# HEBoard_AFE.net
KiCad netlist of a schematic drawn in Altium Designer
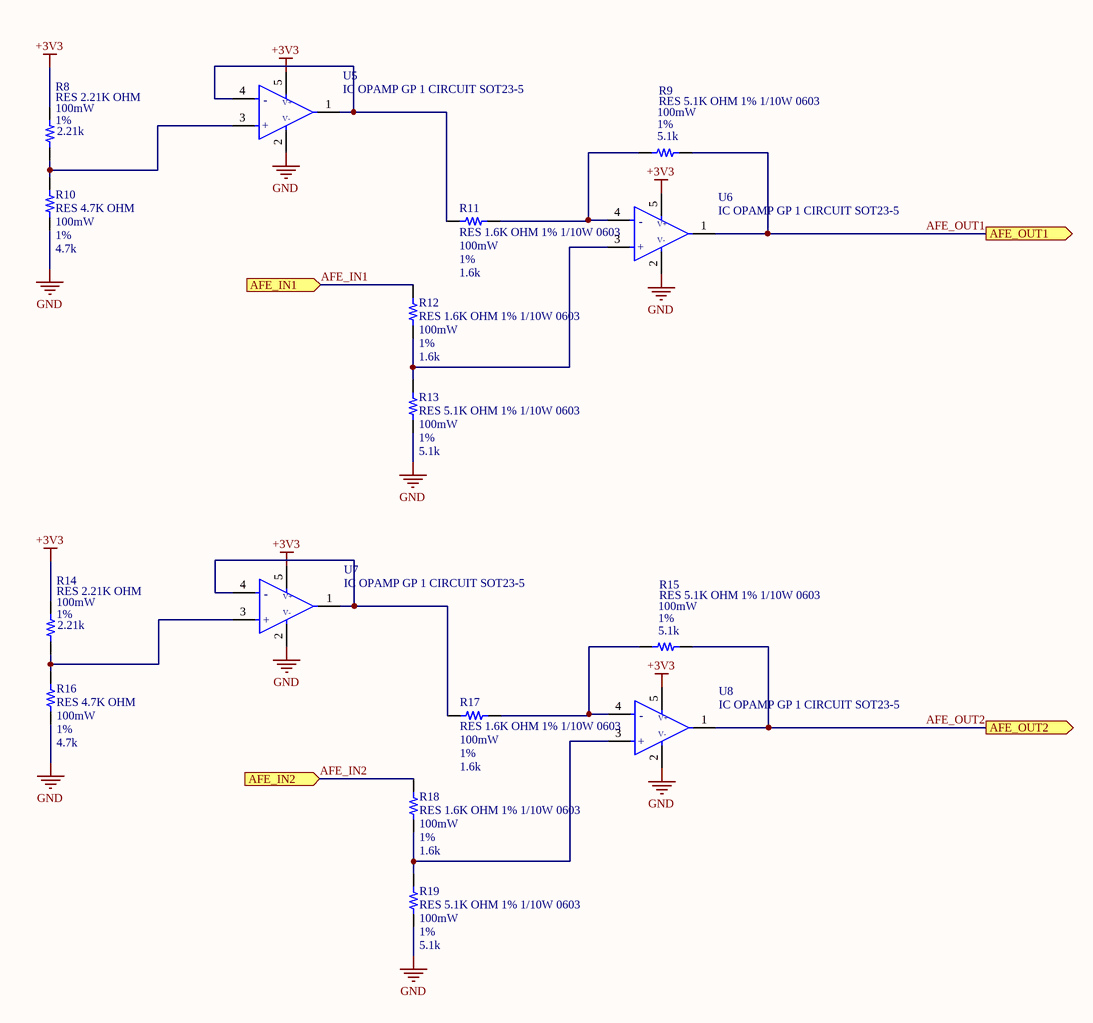
[diagram p0: HEBoard_AFE.SchDoc]

(export (version "E")
  (design (tool "Eeschema 10.0.6"))
  (components
    (comp (ref "R8")
      (value "RES 2.21K OHM")
      (footprint "RES 0603_1608")
      (fields
        (field (name "POWER RATING") "100mW")
        (field (name "TOLERANCE") "1%")
        (field (name "RESISTANCE") "2.21k")
      )
      (libsource (lib "Midnight Sun") (part "Resistor"))
    )
    (comp (ref "R9")
      (value "RES 5.1K OHM 1% 1/10W 0603")
      (footprint "RES 0603_1608")
      (description "5.1 kOhms ±1% 0.1W, 1/10W Chip Resistor 0603 (1608 Metric) Automotive AEC-Q200 Thick Film")
      (fields
        (field (name "POWER RATING") "100mW")
        (field (name "TOLERANCE") "1%")
        (field (name "RESISTANCE") "5.1k")
      )
      (libsource (lib "Midnight Sun") (part "Resistor"))
    )
    (comp (ref "R10")
      (value "RES 4.7K OHM")
      (footprint "RES 0603_1608")
      (fields
        (field (name "POWER RATING") "100mW")
        (field (name "TOLERANCE") "1%")
        (field (name "RESISTANCE") "4.7k")
      )
      (libsource (lib "Midnight Sun") (part "Resistor"))
    )
    (comp (ref "R11")
      (value "RES 1.6K OHM 1% 1/10W 0603")
      (footprint "RES 0603_1608")
      (description "1.6 kOhms ±1% 0.1W, 1/10W Chip Resistor 0603 (1608 Metric) Moisture Resistant Thick Film")
      (fields
        (field (name "POWER RATING") "100mW")
        (field (name "TOLERANCE") "1%")
        (field (name "RESISTANCE") "1.6k")
      )
      (libsource (lib "Midnight Sun") (part "Resistor"))
    )
    (comp (ref "R12")
      (value "RES 1.6K OHM 1% 1/10W 0603")
      (footprint "RES 0603_1608")
      (description "1.6 kOhms ±1% 0.1W, 1/10W Chip Resistor 0603 (1608 Metric) Moisture Resistant Thick Film")
      (fields
        (field (name "POWER RATING") "100mW")
        (field (name "TOLERANCE") "1%")
        (field (name "RESISTANCE") "1.6k")
      )
      (libsource (lib "Midnight Sun") (part "Resistor"))
    )
    (comp (ref "R13")
      (value "RES 5.1K OHM 1% 1/10W 0603")
      (footprint "RES 0603_1608")
      (description "5.1 kOhms ±1% 0.1W, 1/10W Chip Resistor 0603 (1608 Metric) Automotive AEC-Q200 Thick Film")
      (fields
        (field (name "POWER RATING") "100mW")
        (field (name "TOLERANCE") "1%")
        (field (name "RESISTANCE") "5.1k")
      )
      (libsource (lib "Midnight Sun") (part "Resistor"))
    )
    (comp (ref "R14")
      (value "RES 2.21K OHM")
      (footprint "RES 0603_1608")
      (fields
        (field (name "POWER RATING") "100mW")
        (field (name "TOLERANCE") "1%")
        (field (name "RESISTANCE") "2.21k")
      )
      (libsource (lib "Midnight Sun") (part "Resistor"))
    )
    (comp (ref "R15")
      (value "RES 5.1K OHM 1% 1/10W 0603")
      (footprint "RES 0603_1608")
      (description "5.1 kOhms ±1% 0.1W, 1/10W Chip Resistor 0603 (1608 Metric) Automotive AEC-Q200 Thick Film")
      (fields
        (field (name "POWER RATING") "100mW")
        (field (name "TOLERANCE") "1%")
        (field (name "RESISTANCE") "5.1k")
      )
      (libsource (lib "Midnight Sun") (part "Resistor"))
    )
    (comp (ref "R16")
      (value "RES 4.7K OHM")
      (footprint "RES 0603_1608")
      (fields
        (field (name "POWER RATING") "100mW")
        (field (name "TOLERANCE") "1%")
        (field (name "RESISTANCE") "4.7k")
      )
      (libsource (lib "Midnight Sun") (part "Resistor"))
    )
    (comp (ref "R17")
      (value "RES 1.6K OHM 1% 1/10W 0603")
      (footprint "RES 0603_1608")
      (description "1.6 kOhms ±1% 0.1W, 1/10W Chip Resistor 0603 (1608 Metric) Moisture Resistant Thick Film")
      (fields
        (field (name "POWER RATING") "100mW")
        (field (name "TOLERANCE") "1%")
        (field (name "RESISTANCE") "1.6k")
      )
      (libsource (lib "Midnight Sun") (part "Resistor"))
    )
    (comp (ref "R18")
      (value "RES 1.6K OHM 1% 1/10W 0603")
      (footprint "RES 0603_1608")
      (description "1.6 kOhms ±1% 0.1W, 1/10W Chip Resistor 0603 (1608 Metric) Moisture Resistant Thick Film")
      (fields
        (field (name "POWER RATING") "100mW")
        (field (name "TOLERANCE") "1%")
        (field (name "RESISTANCE") "1.6k")
      )
      (libsource (lib "Midnight Sun") (part "Resistor"))
    )
    (comp (ref "R19")
      (value "RES 5.1K OHM 1% 1/10W 0603")
      (footprint "RES 0603_1608")
      (description "5.1 kOhms ±1% 0.1W, 1/10W Chip Resistor 0603 (1608 Metric) Automotive AEC-Q200 Thick Film")
      (fields
        (field (name "POWER RATING") "100mW")
        (field (name "TOLERANCE") "1%")
        (field (name "RESISTANCE") "5.1k")
      )
      (libsource (lib "Midnight Sun") (part "Resistor"))
    )
    (comp (ref "U5")
      (value "IC OPAMP GP 1 CIRCUIT SOT23-5")
      (footprint "SOT 23-5")
      (description "General Purpose Amplifier 1 Circuit Rail-to-Rail SOT-23-5")
      (fields (field (name "MANUFACTURER PART NUMBER") "TLV9051IDBVR"))
      (libsource (lib "Midnight Sun") (part "Op-Amp 5pin-1"))
    )
    (comp (ref "U6")
      (value "IC OPAMP GP 1 CIRCUIT SOT23-5")
      (footprint "SOT 23-5")
      (description "General Purpose Amplifier 1 Circuit Rail-to-Rail SOT-23-5")
      (fields (field (name "MANUFACTURER PART NUMBER") "TLV9051IDBVR"))
      (libsource (lib "Midnight Sun") (part "Op-Amp 5pin-1"))
    )
    (comp (ref "U7")
      (value "IC OPAMP GP 1 CIRCUIT SOT23-5")
      (footprint "SOT 23-5")
      (description "General Purpose Amplifier 1 Circuit Rail-to-Rail SOT-23-5")
      (fields (field (name "MANUFACTURER PART NUMBER") "TLV9051IDBVR"))
      (libsource (lib "Midnight Sun") (part "Op-Amp 5pin-1"))
    )
    (comp (ref "U8")
      (value "IC OPAMP GP 1 CIRCUIT SOT23-5")
      (footprint "SOT 23-5")
      (description "General Purpose Amplifier 1 Circuit Rail-to-Rail SOT-23-5")
      (fields (field (name "MANUFACTURER PART NUMBER") "TLV9051IDBVR"))
      (libsource (lib "Midnight Sun") (part "Op-Amp 5pin-1"))
    )
  )
  (nets
    (net (code "1") (name "+3V3") (class "Default")
      (node (ref "R14") (pin "1") (pinfunction "1_1") (pintype "passive"))
      (node (ref "R8") (pin "1") (pinfunction "1_1") (pintype "passive"))
      (node (ref "U5") (pin "5") (pinfunction "V+_5") (pintype "power_in"))
      (node (ref "U6") (pin "5") (pinfunction "V+_5") (pintype "power_in"))
      (node (ref "U7") (pin "5") (pinfunction "V+_5") (pintype "power_in"))
      (node (ref "U8") (pin "5") (pinfunction "V+_5") (pintype "power_in"))
    )
    (net (code "2") (name "/AFE_IN1") (class "Default")
      (node (ref "R12") (pin "2") (pinfunction "2_2") (pintype "passive"))
    )
    (net (code "3") (name "/AFE_IN2") (class "Default")
      (node (ref "R18") (pin "2") (pinfunction "2_2") (pintype "passive"))
    )
    (net (code "4") (name "/AFE_OUT1") (class "Default")
      (node (ref "R9") (pin "2") (pinfunction "2_2") (pintype "passive"))
      (node (ref "U6") (pin "1") (pinfunction "OUT_1") (pintype "passive"))
    )
    (net (code "5") (name "/AFE_OUT2") (class "Default")
      (node (ref "R15") (pin "2") (pinfunction "2_2") (pintype "passive"))
      (node (ref "U8") (pin "1") (pinfunction "OUT_1") (pintype "passive"))
    )
    (net (code "6") (name "GND") (class "Default")
      (node (ref "R10") (pin "2") (pinfunction "2_2") (pintype "passive"))
      (node (ref "R13") (pin "1") (pinfunction "1_1") (pintype "passive"))
      (node (ref "R16") (pin "2") (pinfunction "2_2") (pintype "passive"))
      (node (ref "R19") (pin "1") (pinfunction "1_1") (pintype "passive"))
      (node (ref "U5") (pin "2") (pinfunction "V-_2") (pintype "power_in"))
      (node (ref "U6") (pin "2") (pinfunction "V-_2") (pintype "power_in"))
      (node (ref "U7") (pin "2") (pinfunction "V-_2") (pintype "power_in"))
      (node (ref "U8") (pin "2") (pinfunction "V-_2") (pintype "power_in"))
    )
    (net (code "7") (name "Net-(U5-IN+)") (class "Default")
      (node (ref "R10") (pin "1") (pinfunction "1_1") (pintype "passive"))
      (node (ref "R8") (pin "2") (pinfunction "2_2") (pintype "passive"))
      (node (ref "U5") (pin "3") (pinfunction "IN+_3") (pintype "tri_state"))
    )
    (net (code "8") (name "Net-(U5-IN-)") (class "Default")
      (node (ref "R11") (pin "2") (pinfunction "2_2") (pintype "passive"))
      (node (ref "U5") (pin "1") (pinfunction "OUT_1") (pintype "passive"))
      (node (ref "U5") (pin "4") (pinfunction "IN-_4") (pintype "tri_state"))
    )
    (net (code "9") (name "Net-(U6-IN+)") (class "Default")
      (node (ref "R12") (pin "1") (pinfunction "1_1") (pintype "passive"))
      (node (ref "R13") (pin "2") (pinfunction "2_2") (pintype "passive"))
      (node (ref "U6") (pin "3") (pinfunction "IN+_3") (pintype "tri_state"))
    )
    (net (code "10") (name "Net-(U6-IN-)") (class "Default")
      (node (ref "R11") (pin "1") (pinfunction "1_1") (pintype "passive"))
      (node (ref "R9") (pin "1") (pinfunction "1_1") (pintype "passive"))
      (node (ref "U6") (pin "4") (pinfunction "IN-_4") (pintype "tri_state"))
    )
    (net (code "11") (name "Net-(U7-IN+)") (class "Default")
      (node (ref "R14") (pin "2") (pinfunction "2_2") (pintype "passive"))
      (node (ref "R16") (pin "1") (pinfunction "1_1") (pintype "passive"))
      (node (ref "U7") (pin "3") (pinfunction "IN+_3") (pintype "tri_state"))
    )
    (net (code "12") (name "Net-(U7-IN-)") (class "Default")
      (node (ref "R17") (pin "2") (pinfunction "2_2") (pintype "passive"))
      (node (ref "U7") (pin "1") (pinfunction "OUT_1") (pintype "passive"))
      (node (ref "U7") (pin "4") (pinfunction "IN-_4") (pintype "tri_state"))
    )
    (net (code "13") (name "Net-(U8-IN+)") (class "Default")
      (node (ref "R18") (pin "1") (pinfunction "1_1") (pintype "passive"))
      (node (ref "R19") (pin "2") (pinfunction "2_2") (pintype "passive"))
      (node (ref "U8") (pin "3") (pinfunction "IN+_3") (pintype "tri_state"))
    )
    (net (code "14") (name "Net-(U8-IN-)") (class "Default")
      (node (ref "R15") (pin "1") (pinfunction "1_1") (pintype "passive"))
      (node (ref "R17") (pin "1") (pinfunction "1_1") (pintype "passive"))
      (node (ref "U8") (pin "4") (pinfunction "IN-_4") (pintype "tri_state"))
    )
  )
)
